# kwpa_ldmos2.net
KiCad netlist of a schematic drawn in EAGLE
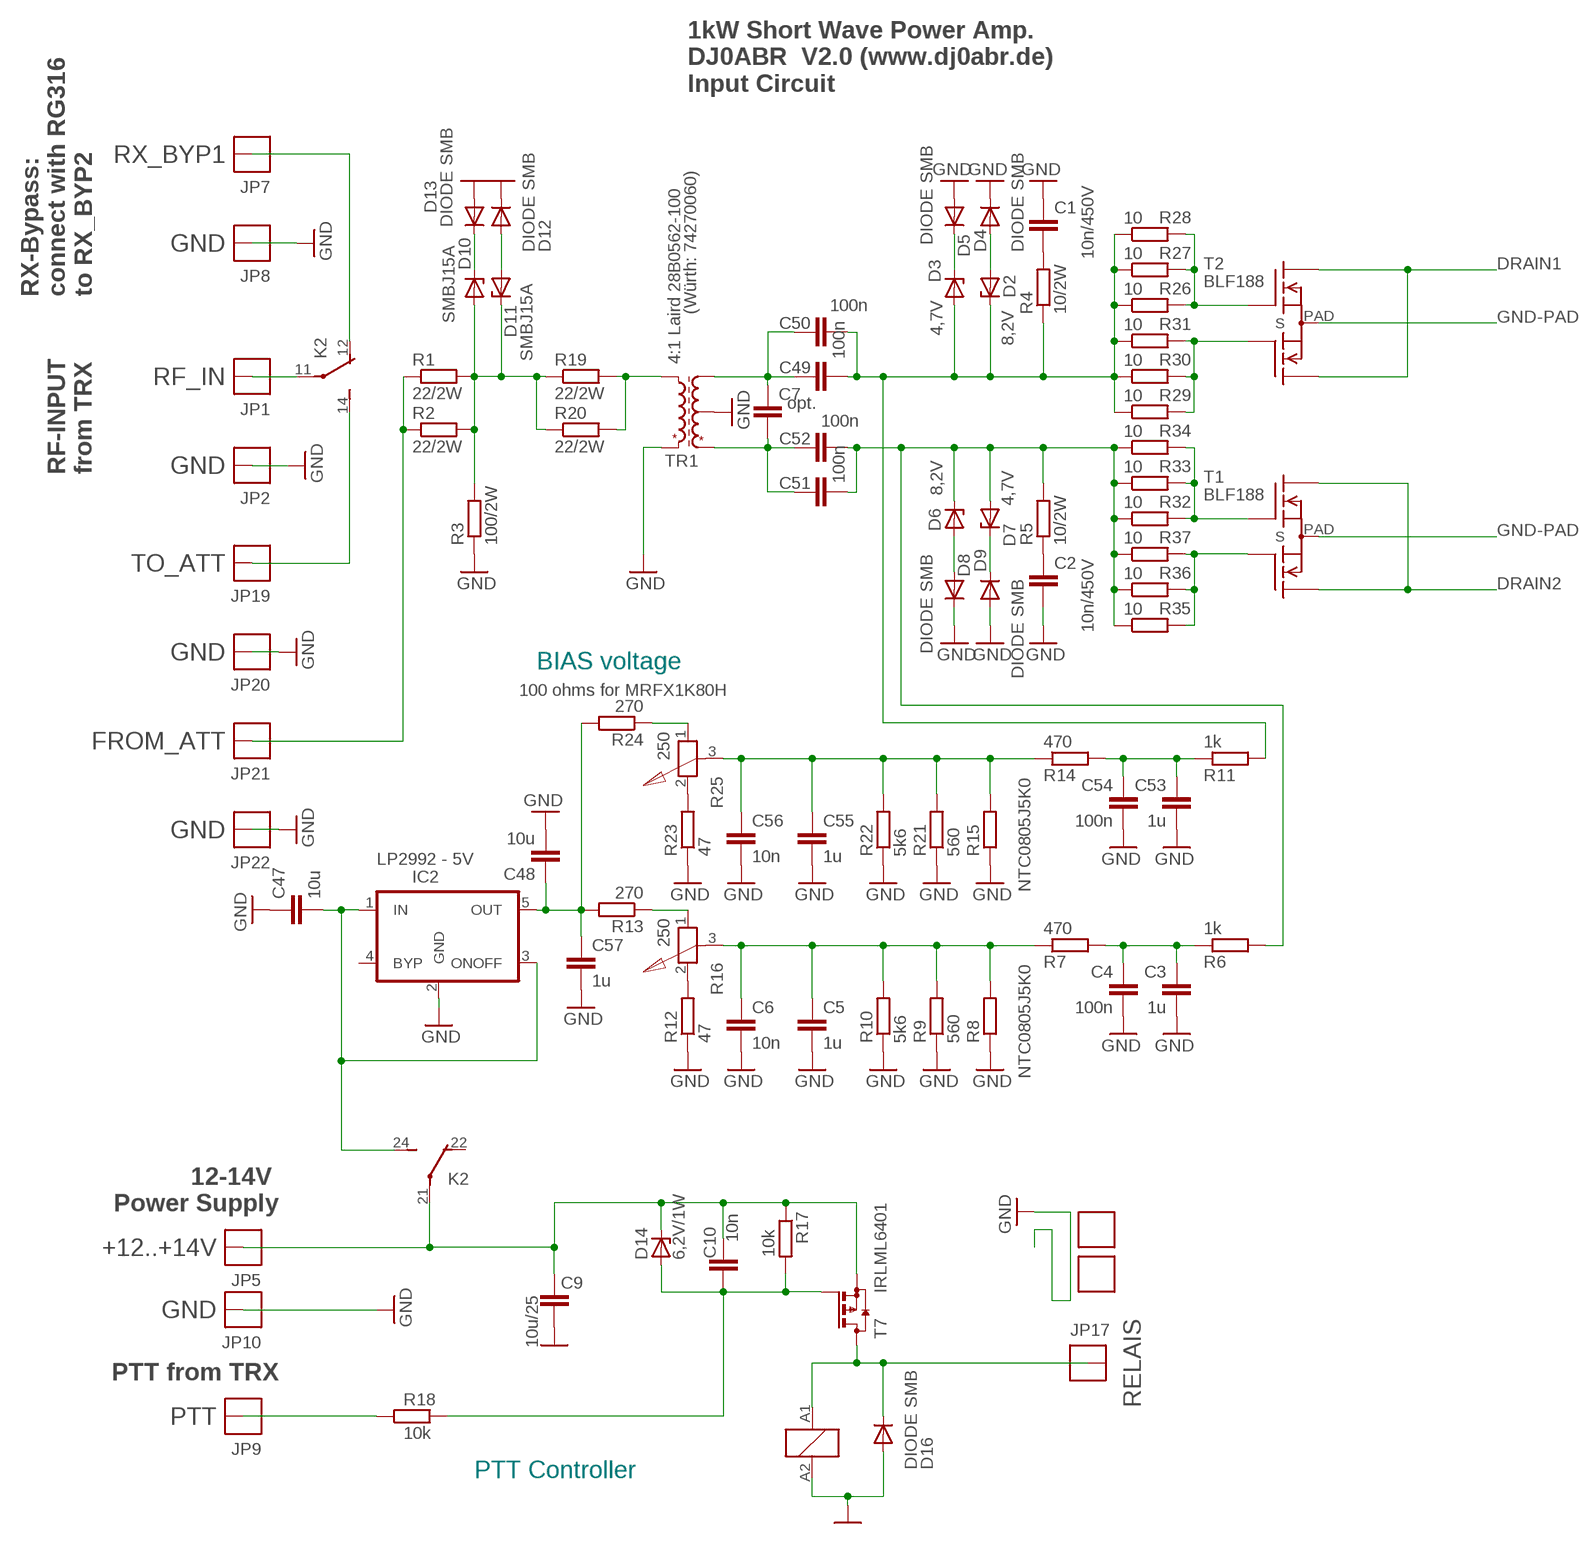
[diagram p0: schematic, sheet 1]
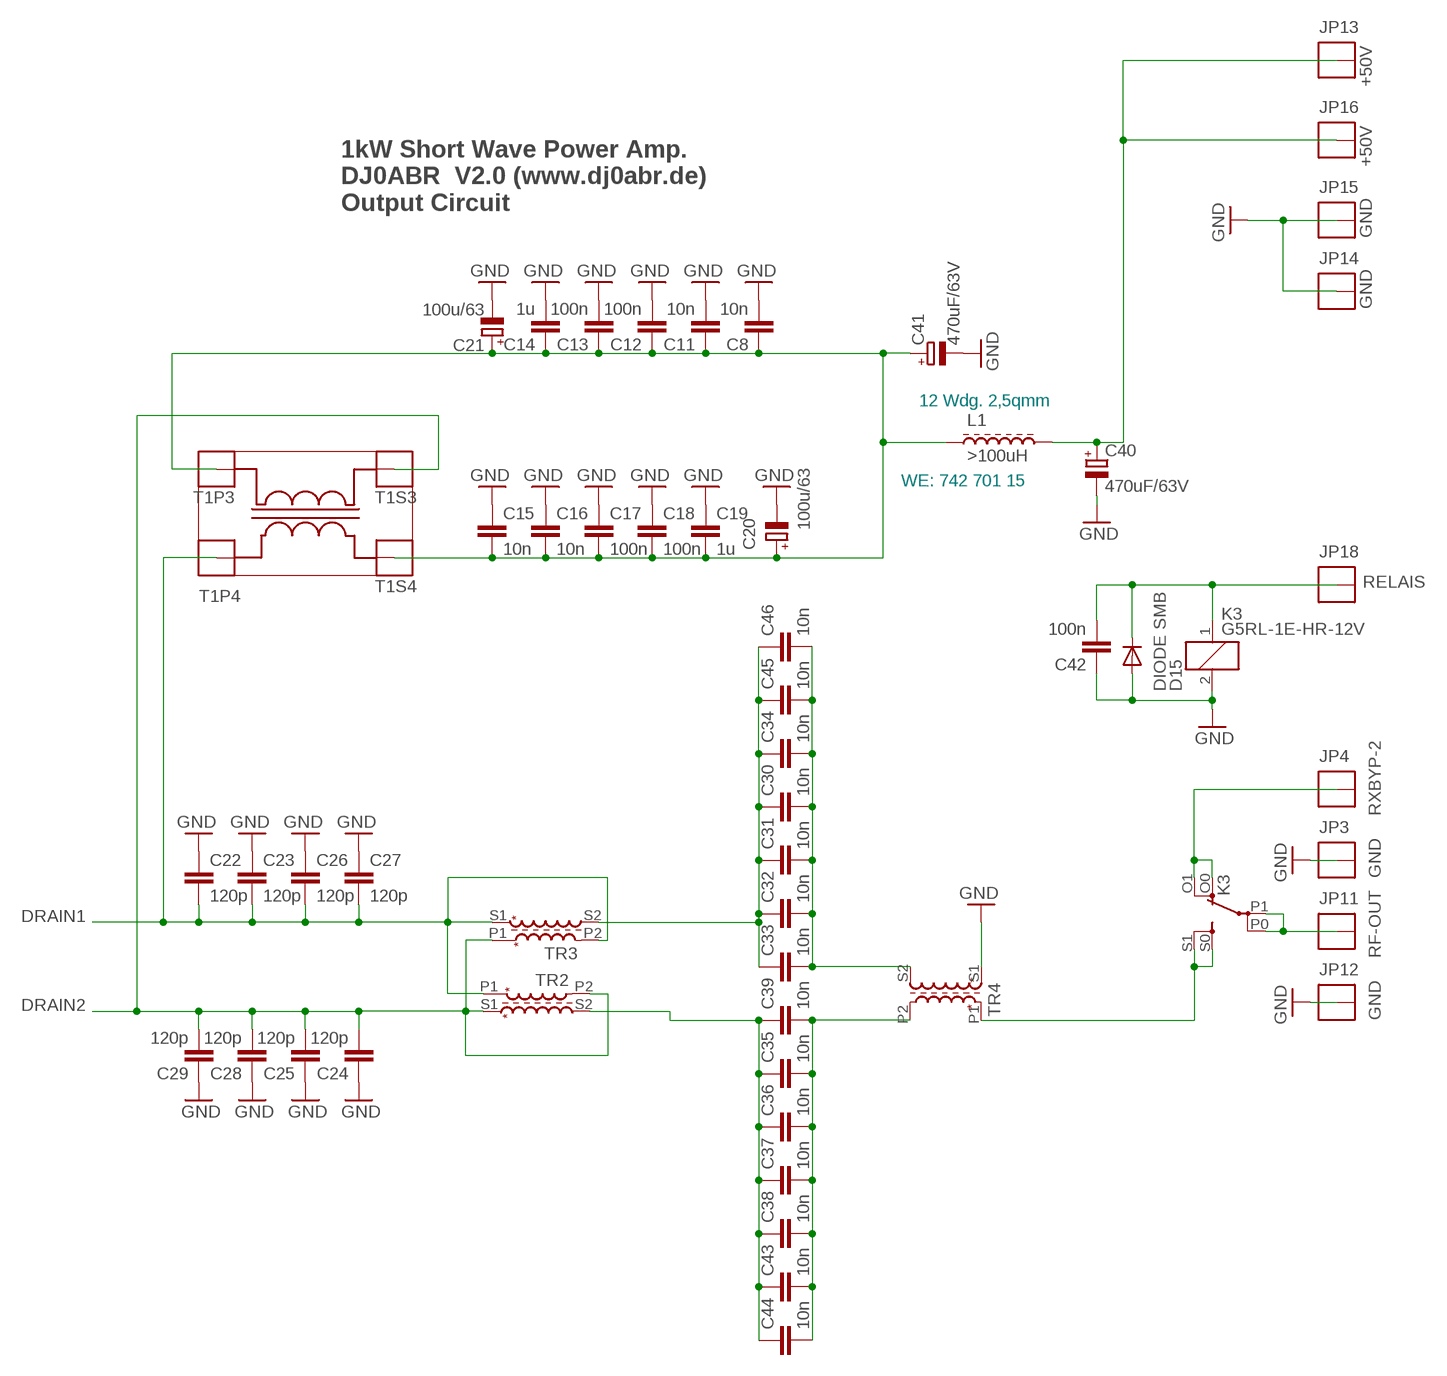
[diagram p1: schematic, sheet 2]

(export (version "E")
  (design (tool "Eeschema 10.0.6"))
  (components
    (comp (ref "C8")
      (value "10n")
      (footprint "eagle-import:C1812K")
      (libsource (lib "eagle-import") (part "C-EUC1812K"))
    )
    (comp (ref "C11")
      (value "10n")
      (footprint "eagle-import:C1812K")
      (libsource (lib "eagle-import") (part "C-EUC1812K"))
    )
    (comp (ref "C12")
      (value "100n")
      (footprint "eagle-import:C1812K")
      (libsource (lib "eagle-import") (part "C-EUC1812K"))
    )
    (comp (ref "C13")
      (value "100n")
      (footprint "eagle-import:C1812K")
      (libsource (lib "eagle-import") (part "C-EUC1812K"))
    )
    (comp (ref "C14")
      (value "1u")
      (footprint "eagle-import:C1812K")
      (libsource (lib "eagle-import") (part "C-EUC1812K"))
    )
    (comp (ref "C15")
      (value "10n")
      (footprint "eagle-import:C1812K")
      (libsource (lib "eagle-import") (part "C-EUC1812K"))
    )
    (comp (ref "C16")
      (value "10n")
      (footprint "eagle-import:C1812K")
      (libsource (lib "eagle-import") (part "C-EUC1812K"))
    )
    (comp (ref "C17")
      (value "100n")
      (footprint "eagle-import:C1812K")
      (libsource (lib "eagle-import") (part "C-EUC1812K"))
    )
    (comp (ref "C18")
      (value "100n")
      (footprint "eagle-import:C1812K")
      (libsource (lib "eagle-import") (part "C-EUC1812K"))
    )
    (comp (ref "C19")
      (value "1u")
      (footprint "eagle-import:C1812K")
      (libsource (lib "eagle-import") (part "C-EUC1812K"))
    )
    (comp (ref "C20")
      (value "100u/63")
      (footprint "eagle-import:153CLV-1014")
      (libsource (lib "eagle-import") (part "CPOL-EU153CLV-1014"))
    )
    (comp (ref "C21")
      (value "100u/63")
      (footprint "eagle-import:153CLV-1014")
      (libsource (lib "eagle-import") (part "CPOL-EU153CLV-1014"))
    )
    (comp (ref "C22")
      (value "120p")
      (footprint "eagle-import:C1812K")
      (libsource (lib "eagle-import") (part "C-EUC1812K"))
    )
    (comp (ref "C23")
      (value "120p")
      (footprint "eagle-import:C1812K")
      (libsource (lib "eagle-import") (part "C-EUC1812K"))
    )
    (comp (ref "C24")
      (value "120p")
      (footprint "eagle-import:C1812K")
      (libsource (lib "eagle-import") (part "C-EUC1812K"))
    )
    (comp (ref "C25")
      (value "120p")
      (footprint "eagle-import:C1812K")
      (libsource (lib "eagle-import") (part "C-EUC1812K"))
    )
    (comp (ref "C26")
      (value "120p")
      (footprint "eagle-import:C1812K")
      (libsource (lib "eagle-import") (part "C-EUC1812K"))
    )
    (comp (ref "C27")
      (value "120p")
      (footprint "eagle-import:C1812K")
      (libsource (lib "eagle-import") (part "C-EUC1812K"))
    )
    (comp (ref "C28")
      (value "120p")
      (footprint "eagle-import:C1812K")
      (libsource (lib "eagle-import") (part "C-EUC1812K"))
    )
    (comp (ref "C29")
      (value "120p")
      (footprint "eagle-import:C1812K")
      (libsource (lib "eagle-import") (part "C-EUC1812K"))
    )
    (comp (ref "C30")
      (value "10n")
      (footprint "eagle-import:C1210K")
      (libsource (lib "eagle-import") (part "C-EUC1210K"))
    )
    (comp (ref "C31")
      (value "10n")
      (footprint "eagle-import:C1210K")
      (libsource (lib "eagle-import") (part "C-EUC1210K"))
    )
    (comp (ref "C32")
      (value "10n")
      (footprint "eagle-import:C1210K")
      (libsource (lib "eagle-import") (part "C-EUC1210K"))
    )
    (comp (ref "C33")
      (value "10n")
      (footprint "eagle-import:C1210K")
      (libsource (lib "eagle-import") (part "C-EUC1210K"))
    )
    (comp (ref "C34")
      (value "10n")
      (footprint "eagle-import:C1210K")
      (libsource (lib "eagle-import") (part "C-EUC1210K"))
    )
    (comp (ref "C35")
      (value "10n")
      (footprint "eagle-import:C1210K")
      (libsource (lib "eagle-import") (part "C-EUC1210K"))
    )
    (comp (ref "C36")
      (value "10n")
      (footprint "eagle-import:C1210K")
      (libsource (lib "eagle-import") (part "C-EUC1210K"))
    )
    (comp (ref "C37")
      (value "10n")
      (footprint "eagle-import:C1210K")
      (libsource (lib "eagle-import") (part "C-EUC1210K"))
    )
    (comp (ref "C38")
      (value "10n")
      (footprint "eagle-import:C1210K")
      (libsource (lib "eagle-import") (part "C-EUC1210K"))
    )
    (comp (ref "C39")
      (value "10n")
      (footprint "eagle-import:C1210K")
      (libsource (lib "eagle-import") (part "C-EUC1210K"))
    )
    (comp (ref "C40")
      (value "470uF/63V")
      (footprint "eagle-import:E5-13")
      (libsource (lib "eagle-import") (part "CPOL-EUE5-13"))
    )
    (comp (ref "C41")
      (value "470uF/63V")
      (footprint "eagle-import:E5-13")
      (libsource (lib "eagle-import") (part "CPOL-EUE5-13"))
    )
    (comp (ref "C42")
      (value "100n")
      (footprint "eagle-import:C0603K")
      (libsource (lib "eagle-import") (part "C-EUC0603K"))
    )
    (comp (ref "C43")
      (value "10n")
      (footprint "eagle-import:C1210K")
      (libsource (lib "eagle-import") (part "C-EUC1210K"))
    )
    (comp (ref "C44")
      (value "10n")
      (footprint "eagle-import:C1210K")
      (libsource (lib "eagle-import") (part "C-EUC1210K"))
    )
    (comp (ref "C45")
      (value "10n")
      (footprint "eagle-import:C1210K")
      (libsource (lib "eagle-import") (part "C-EUC1210K"))
    )
    (comp (ref "C46")
      (value "10n")
      (footprint "eagle-import:C1210K")
      (libsource (lib "eagle-import") (part "C-EUC1210K"))
    )
    (comp (ref "D15")
      (value "DIODE SMB")
      (footprint "eagle-import:SMB")
      (libsource (lib "eagle-import") (part "DIODE-SMB"))
    )
    (comp (ref "JP3")
      (value "GND")
      (footprint "eagle-import:THICKPIN")
      (libsource (lib "eagle-import") (part "THICKPINSQUARE"))
    )
    (comp (ref "JP4")
      (value "RXBYP-2")
      (footprint "eagle-import:THICKPIN")
      (libsource (lib "eagle-import") (part "THICKPINSQUARE"))
    )
    (comp (ref "JP11")
      (value "RF-OUT")
      (footprint "eagle-import:THICKPIN")
      (libsource (lib "eagle-import") (part "THICKPINSQUARE"))
    )
    (comp (ref "JP12")
      (value "GND")
      (footprint "eagle-import:THICKPIN")
      (libsource (lib "eagle-import") (part "THICKPINSQUARE"))
    )
    (comp (ref "JP13")
      (value "+50V")
      (footprint "eagle-import:THICKPIN")
      (libsource (lib "eagle-import") (part "THICKPINSQUARE"))
    )
    (comp (ref "JP14")
      (value "GND")
      (footprint "eagle-import:THICKPIN")
      (libsource (lib "eagle-import") (part "THICKPINSQUARE"))
    )
    (comp (ref "JP15")
      (value "GND")
      (footprint "eagle-import:THICKPIN")
      (libsource (lib "eagle-import") (part "THICKPINSQUARE"))
    )
    (comp (ref "JP16")
      (value "+50V")
      (footprint "eagle-import:THICKPIN")
      (libsource (lib "eagle-import") (part "THICKPINSQUARE"))
    )
    (comp (ref "JP18")
      (value "RELAIS")
      (footprint "eagle-import:THICKPIN")
      (libsource (lib "eagle-import") (part "THICKPINSQUARE"))
    )
    (comp (ref "K3")
      (value "G5RL-1E-HR-12V")
      (footprint "eagle-import:G2RE")
      (libsource (lib "eagle-import") (part "G2RE"))
    )
    (comp (ref "L1")
      (value ">100uH")
      (footprint "eagle-import:KERN90_STEHEND_2PIN")
      (libsource (lib "eagle-import") (part "SPULE_1W30X12"))
    )
    (comp (ref "T1P3")
      (value "THICKPINSMD2,5X4")
      (footprint "eagle-import:SMDPAD2,5X4")
      (libsource (lib "eagle-import") (part "THICKPINSMD2,5X4"))
    )
    (comp (ref "T1P4")
      (value "THICKPINSMD2,5X4")
      (footprint "eagle-import:SMDPAD2,5X4")
      (libsource (lib "eagle-import") (part "THICKPINSMD2,5X4"))
    )
    (comp (ref "T1S3")
      (value "THICKPINSMD2,5X4")
      (footprint "eagle-import:SMDPAD2,5X4")
      (libsource (lib "eagle-import") (part "THICKPINSMD2,5X4"))
    )
    (comp (ref "T1S4")
      (value "THICKPINSMD2,5X4")
      (footprint "eagle-import:SMDPAD2,5X4")
      (libsource (lib "eagle-import") (part "THICKPINSMD2,5X4"))
    )
    (comp (ref "TR2")
      (value "TRAFO_1W_1W_GERADE_DOPPELROHR")
      (footprint "eagle-import:DOPPELRINGKERN")
      (libsource (lib "eagle-import") (part "TRAFO_1W_1W_GERADE_DOPPELROHR"))
    )
    (comp (ref "TR3")
      (value "TRAFO_1W_1W_GERADE_DOPPELROHRREVERSE")
      (footprint "eagle-import:DOPPELRINGKERN_REV")
      (libsource (lib "eagle-import") (part "TRAFO_1W_1W_GERADE_DOPPELROHRREVERSE"))
    )
    (comp (ref "TR4")
      (value "TRAFO_1W_1WMANTEL_STEHEND")
      (footprint "eagle-import:DOPPELLMANTEL_STEHEND")
      (libsource (lib "eagle-import") (part "TRAFO_1W_1WMANTEL_STEHEND"))
    )
    (comp (ref "C1")
      (value "10n/450V")
      (footprint "eagle-import:C1206K")
      (libsource (lib "eagle-import") (part "C-EUC1206K"))
    )
    (comp (ref "C2")
      (value "10n/450V")
      (footprint "eagle-import:C1206K")
      (libsource (lib "eagle-import") (part "C-EUC1206K"))
    )
    (comp (ref "C3")
      (value "1u")
      (footprint "eagle-import:C0603K")
      (libsource (lib "eagle-import") (part "C-EUC0603K"))
    )
    (comp (ref "C4")
      (value "100n")
      (footprint "eagle-import:C0603K")
      (libsource (lib "eagle-import") (part "C-EUC0603K"))
    )
    (comp (ref "C5")
      (value "1u")
      (footprint "eagle-import:C0603K")
      (libsource (lib "eagle-import") (part "C-EUC0603K"))
    )
    (comp (ref "C6")
      (value "10n")
      (footprint "eagle-import:C0603K")
      (libsource (lib "eagle-import") (part "C-EUC0603K"))
    )
    (comp (ref "C7")
      (value "opt.")
      (footprint "eagle-import:C1206K")
      (libsource (lib "eagle-import") (part "C-EUC1206K"))
    )
    (comp (ref "C9")
      (value "10u/25")
      (footprint "eagle-import:C0805K")
      (libsource (lib "eagle-import") (part "C-EUC0805K"))
    )
    (comp (ref "C10")
      (value "10n")
      (footprint "eagle-import:C0603K")
      (libsource (lib "eagle-import") (part "C-EUC0603K"))
    )
    (comp (ref "C47")
      (value "10u")
      (footprint "eagle-import:C0805K")
      (libsource (lib "eagle-import") (part "C-EUC0805K"))
    )
    (comp (ref "C48")
      (value "10u")
      (footprint "eagle-import:C0603K")
      (libsource (lib "eagle-import") (part "C-EUC0603K"))
    )
    (comp (ref "C49")
      (value "100n")
      (footprint "eagle-import:C1812K")
      (libsource (lib "eagle-import") (part "C-EUC1812K"))
    )
    (comp (ref "C50")
      (value "100n")
      (footprint "eagle-import:C1812K")
      (libsource (lib "eagle-import") (part "C-EUC1812K"))
    )
    (comp (ref "C51")
      (value "100n")
      (footprint "eagle-import:C1812K")
      (libsource (lib "eagle-import") (part "C-EUC1812K"))
    )
    (comp (ref "C52")
      (value "100n")
      (footprint "eagle-import:C1812K")
      (libsource (lib "eagle-import") (part "C-EUC1812K"))
    )
    (comp (ref "C53")
      (value "1u")
      (footprint "eagle-import:C0603K")
      (libsource (lib "eagle-import") (part "C-EUC0603K"))
    )
    (comp (ref "C54")
      (value "100n")
      (footprint "eagle-import:C0603K")
      (libsource (lib "eagle-import") (part "C-EUC0603K"))
    )
    (comp (ref "C55")
      (value "1u")
      (footprint "eagle-import:C0603K")
      (libsource (lib "eagle-import") (part "C-EUC0603K"))
    )
    (comp (ref "C56")
      (value "10n")
      (footprint "eagle-import:C0603K")
      (libsource (lib "eagle-import") (part "C-EUC0603K"))
    )
    (comp (ref "C57")
      (value "1u")
      (footprint "eagle-import:C0603K")
      (libsource (lib "eagle-import") (part "C-EUC0603K"))
    )
    (comp (ref "D2")
      (value "8,2V")
      (footprint "eagle-import:SMA")
      (libsource (lib "eagle-import") (part "ZPYSMA"))
    )
    (comp (ref "D3")
      (value "4,7V")
      (footprint "eagle-import:SMA")
      (libsource (lib "eagle-import") (part "ZPYSMA"))
    )
    (comp (ref "D4")
      (value "DIODE SMB")
      (footprint "eagle-import:SMB")
      (libsource (lib "eagle-import") (part "DIODE-SMB"))
    )
    (comp (ref "D5")
      (value "DIODE SMB")
      (footprint "eagle-import:SMB")
      (libsource (lib "eagle-import") (part "DIODE-SMB"))
    )
    (comp (ref "D6")
      (value "8,2V")
      (footprint "eagle-import:SMA")
      (libsource (lib "eagle-import") (part "ZPYSMA"))
    )
    (comp (ref "D7")
      (value "4,7V")
      (footprint "eagle-import:SMA")
      (libsource (lib "eagle-import") (part "ZPYSMA"))
    )
    (comp (ref "D8")
      (value "DIODE SMB")
      (footprint "eagle-import:SMB")
      (libsource (lib "eagle-import") (part "DIODE-SMB"))
    )
    (comp (ref "D9")
      (value "DIODE SMB")
      (footprint "eagle-import:SMB")
      (libsource (lib "eagle-import") (part "DIODE-SMB"))
    )
    (comp (ref "D10")
      (value "SMBJ15A")
      (footprint "eagle-import:SMA")
      (libsource (lib "eagle-import") (part "ZPYSMA"))
    )
    (comp (ref "D11")
      (value "SMBJ15A")
      (footprint "eagle-import:SMA")
      (libsource (lib "eagle-import") (part "ZPYSMA"))
    )
    (comp (ref "D12")
      (value "DIODE SMB")
      (footprint "eagle-import:SMB")
      (libsource (lib "eagle-import") (part "DIODE-SMB"))
    )
    (comp (ref "D13")
      (value "DIODE SMB")
      (footprint "eagle-import:SMB")
      (libsource (lib "eagle-import") (part "DIODE-SMB"))
    )
    (comp (ref "D14")
      (value "6,2V/1W")
      (footprint "eagle-import:SMA")
      (libsource (lib "eagle-import") (part "ZPYSMA"))
    )
    (comp (ref "D16")
      (value "DIODE SMB")
      (footprint "eagle-import:SMB")
      (libsource (lib "eagle-import") (part "DIODE-SMB"))
    )
    (comp (ref "FID1")
      (value "FIDUCIAL")
      (footprint "eagle-import:FIDUCIAL")
      (libsource (lib "eagle-import") (part "FIDUCIAL"))
    )
    (comp (ref "FID2")
      (value "FIDUCIAL")
      (footprint "eagle-import:FIDUCIAL")
      (libsource (lib "eagle-import") (part "FIDUCIAL"))
    )
    (comp (ref "H1")
      (value "HOLE_32")
      (footprint "eagle-import:HOLE32")
      (libsource (lib "eagle-import") (part "HOLE_32"))
    )
    (comp (ref "H2")
      (value "HOLE_32")
      (footprint "eagle-import:HOLE32")
      (libsource (lib "eagle-import") (part "HOLE_32"))
    )
    (comp (ref "H3")
      (value "HOLE_32")
      (footprint "eagle-import:HOLE32")
      (libsource (lib "eagle-import") (part "HOLE_32"))
    )
    (comp (ref "H4")
      (value "HOLE_32")
      (footprint "eagle-import:HOLE32")
      (libsource (lib "eagle-import") (part "HOLE_32"))
    )
    (comp (ref "H5")
      (value "HOLE_32")
      (footprint "eagle-import:HOLE32")
      (libsource (lib "eagle-import") (part "HOLE_32"))
    )
    (comp (ref "H6")
      (value "HOLE_32")
      (footprint "eagle-import:HOLE32")
      (libsource (lib "eagle-import") (part "HOLE_32"))
    )
    (comp (ref "H7")
      (value "HOLE_32")
      (footprint "eagle-import:HOLE32")
      (libsource (lib "eagle-import") (part "HOLE_32"))
    )
    (comp (ref "H8")
      (value "HOLE_32")
      (footprint "eagle-import:HOLE32")
      (libsource (lib "eagle-import") (part "HOLE_32"))
    )
    (comp (ref "H9")
      (value "HOLE_32")
      (footprint "eagle-import:HOLE32")
      (libsource (lib "eagle-import") (part "HOLE_32"))
    )
    (comp (ref "H10")
      (value "HOLE_32")
      (footprint "eagle-import:HOLE32")
      (libsource (lib "eagle-import") (part "HOLE_32"))
    )
    (comp (ref "H11")
      (value "HOLE_32")
      (footprint "eagle-import:HOLE32")
      (libsource (lib "eagle-import") (part "HOLE_32"))
    )
    (comp (ref "H12")
      (value "HOLE_32")
      (footprint "eagle-import:HOLE32")
      (libsource (lib "eagle-import") (part "HOLE_32"))
    )
    (comp (ref "H13")
      (value "HOLE_32")
      (footprint "eagle-import:HOLE32")
      (libsource (lib "eagle-import") (part "HOLE_32"))
    )
    (comp (ref "H14")
      (value "HOLE_32")
      (footprint "eagle-import:HOLE32")
      (libsource (lib "eagle-import") (part "HOLE_32"))
    )
    (comp (ref "IC2")
      (value "LP2992 - 5V")
      (footprint "eagle-import:SOT23-5")
      (libsource (lib "eagle-import") (part "UREG5"))
    )
    (comp (ref "JP1")
      (value "RF_IN")
      (footprint "eagle-import:THICKPIN")
      (libsource (lib "eagle-import") (part "THICKPINSQUARE"))
    )
    (comp (ref "JP2")
      (value "GND")
      (footprint "eagle-import:THICKPIN")
      (libsource (lib "eagle-import") (part "THICKPINSQUARE"))
    )
    (comp (ref "JP5")
      (value "+12..+14V")
      (footprint "eagle-import:THICKPIN")
      (libsource (lib "eagle-import") (part "THICKPINSQUARE"))
    )
    (comp (ref "JP7")
      (value "RX_BYP1")
      (footprint "eagle-import:THICKPIN")
      (libsource (lib "eagle-import") (part "THICKPINSQUARE"))
    )
    (comp (ref "JP8")
      (value "GND")
      (footprint "eagle-import:THICKPIN")
      (libsource (lib "eagle-import") (part "THICKPINSQUARE"))
    )
    (comp (ref "JP9")
      (value "PTT")
      (footprint "eagle-import:THICKPIN")
      (libsource (lib "eagle-import") (part "THICKPINSQUARE"))
    )
    (comp (ref "JP10")
      (value "GND")
      (footprint "eagle-import:THICKPIN")
      (libsource (lib "eagle-import") (part "THICKPINSQUARE"))
    )
    (comp (ref "JP17")
      (value "RELAIS")
      (footprint "eagle-import:THICKPIN")
      (libsource (lib "eagle-import") (part "THICKPINSQUARE"))
    )
    (comp (ref "JP19")
      (value "TO_ATT")
      (footprint "eagle-import:THICKPIN")
      (libsource (lib "eagle-import") (part "THICKPINSQUARE"))
    )
    (comp (ref "JP20")
      (value "GND")
      (footprint "eagle-import:THICKPIN")
      (libsource (lib "eagle-import") (part "THICKPINSQUARE"))
    )
    (comp (ref "JP21")
      (value "FROM_ATT")
      (footprint "eagle-import:THICKPIN")
      (libsource (lib "eagle-import") (part "THICKPINSQUARE"))
    )
    (comp (ref "JP22")
      (value "GND")
      (footprint "eagle-import:THICKPIN")
      (libsource (lib "eagle-import") (part "THICKPINSQUARE"))
    )
    (comp (ref "K2")
      (value "FINDER-30.22")
      (footprint "eagle-import:FINDER-30.22")
      (libsource (lib "eagle-import") (part "FINDER-30.22"))
    )
    (comp (ref "R1")
      (value "22/2W")
      (footprint "eagle-import:R2512")
      (libsource (lib "eagle-import") (part "R-EU_R2512"))
    )
    (comp (ref "R2")
      (value "22/2W")
      (footprint "eagle-import:R2512")
      (libsource (lib "eagle-import") (part "R-EU_R2512"))
    )
    (comp (ref "R3")
      (value "100/2W")
      (footprint "eagle-import:R2512")
      (libsource (lib "eagle-import") (part "R-EU_R2512"))
    )
    (comp (ref "R4")
      (value "10/2W")
      (footprint "eagle-import:R2512")
      (libsource (lib "eagle-import") (part "R-EU_R2512"))
    )
    (comp (ref "R5")
      (value "10/2W")
      (footprint "eagle-import:R2512")
      (libsource (lib "eagle-import") (part "R-EU_R2512"))
    )
    (comp (ref "R6")
      (value "1k")
      (footprint "eagle-import:R0603")
      (libsource (lib "eagle-import") (part "R-EU_R0603"))
    )
    (comp (ref "R7")
      (value "470")
      (footprint "eagle-import:R0603")
      (libsource (lib "eagle-import") (part "R-EU_R0603"))
    )
    (comp (ref "R8")
      (value "NTC0805J5K0")
      (footprint "eagle-import:R0805")
      (libsource (lib "eagle-import") (part "R-EU_R0805"))
    )
    (comp (ref "R9")
      (value "560")
      (footprint "eagle-import:R0603")
      (libsource (lib "eagle-import") (part "R-EU_R0603"))
    )
    (comp (ref "R10")
      (value "5k6")
      (footprint "eagle-import:R0603")
      (libsource (lib "eagle-import") (part "R-EU_R0603"))
    )
    (comp (ref "R11")
      (value "1k")
      (footprint "eagle-import:R0603")
      (libsource (lib "eagle-import") (part "R-EU_R0603"))
    )
    (comp (ref "R12")
      (value "47")
      (footprint "eagle-import:R0603")
      (libsource (lib "eagle-import") (part "R-EU_R0603"))
    )
    (comp (ref "R13")
      (value "270")
      (footprint "eagle-import:R0603")
      (libsource (lib "eagle-import") (part "R-EU_R0603"))
    )
    (comp (ref "R14")
      (value "470")
      (footprint "eagle-import:R0603")
      (libsource (lib "eagle-import") (part "R-EU_R0603"))
    )
    (comp (ref "R15")
      (value "NTC0805J5K0")
      (footprint "eagle-import:R0805")
      (libsource (lib "eagle-import") (part "R-EU_R0805"))
    )
    (comp (ref "R16")
      (value "250")
      (footprint "eagle-import:MINIPOTI")
      (libsource (lib "eagle-import") (part "MINIPOTI-S"))
    )
    (comp (ref "R17")
      (value "10k")
      (footprint "eagle-import:R0603")
      (libsource (lib "eagle-import") (part "R-EU_R0603"))
    )
    (comp (ref "R18")
      (value "10k")
      (footprint "eagle-import:R0603")
      (libsource (lib "eagle-import") (part "R-EU_R0603"))
    )
    (comp (ref "R19")
      (value "22/2W")
      (footprint "eagle-import:R2512")
      (libsource (lib "eagle-import") (part "R-EU_R2512"))
    )
    (comp (ref "R20")
      (value "22/2W")
      (footprint "eagle-import:R2512")
      (libsource (lib "eagle-import") (part "R-EU_R2512"))
    )
    (comp (ref "R21")
      (value "560")
      (footprint "eagle-import:R0603")
      (libsource (lib "eagle-import") (part "R-EU_R0603"))
    )
    (comp (ref "R22")
      (value "5k6")
      (footprint "eagle-import:R0603")
      (libsource (lib "eagle-import") (part "R-EU_R0603"))
    )
    (comp (ref "R23")
      (value "47")
      (footprint "eagle-import:R0603")
      (libsource (lib "eagle-import") (part "R-EU_R0603"))
    )
    (comp (ref "R24")
      (value "270")
      (footprint "eagle-import:R0603")
      (libsource (lib "eagle-import") (part "R-EU_R0603"))
    )
    (comp (ref "R25")
      (value "250")
      (footprint "eagle-import:MINIPOTI")
      (libsource (lib "eagle-import") (part "MINIPOTI-S"))
    )
    (comp (ref "R26")
      (value "10")
      (footprint "eagle-import:R1206")
      (libsource (lib "eagle-import") (part "R-EU_R1206"))
    )
    (comp (ref "R27")
      (value "10")
      (footprint "eagle-import:R1206")
      (libsource (lib "eagle-import") (part "R-EU_R1206"))
    )
    (comp (ref "R28")
      (value "10")
      (footprint "eagle-import:R1206")
      (libsource (lib "eagle-import") (part "R-EU_R1206"))
    )
    (comp (ref "R29")
      (value "10")
      (footprint "eagle-import:R1206")
      (libsource (lib "eagle-import") (part "R-EU_R1206"))
    )
    (comp (ref "R30")
      (value "10")
      (footprint "eagle-import:R1206")
      (libsource (lib "eagle-import") (part "R-EU_R1206"))
    )
    (comp (ref "R31")
      (value "10")
      (footprint "eagle-import:R1206")
      (libsource (lib "eagle-import") (part "R-EU_R1206"))
    )
    (comp (ref "R32")
      (value "10")
      (footprint "eagle-import:R1206")
      (libsource (lib "eagle-import") (part "R-EU_R1206"))
    )
    (comp (ref "R33")
      (value "10")
      (footprint "eagle-import:R1206")
      (libsource (lib "eagle-import") (part "R-EU_R1206"))
    )
    (comp (ref "R34")
      (value "10")
      (footprint "eagle-import:R1206")
      (libsource (lib "eagle-import") (part "R-EU_R1206"))
    )
    (comp (ref "R35")
      (value "10")
      (footprint "eagle-import:R1206")
      (libsource (lib "eagle-import") (part "R-EU_R1206"))
    )
    (comp (ref "R36")
      (value "10")
      (footprint "eagle-import:R1206")
      (libsource (lib "eagle-import") (part "R-EU_R1206"))
    )
    (comp (ref "R37")
      (value "10")
      (footprint "eagle-import:R1206")
      (libsource (lib "eagle-import") (part "R-EU_R1206"))
    )
    (comp (ref "T1")
      (value "BLF188")
      (footprint "eagle-import:BLF188")
      (libsource (lib "eagle-import") (part "BLF188"))
    )
    (comp (ref "T2")
      (value "BLF188")
      (footprint "eagle-import:BLF188")
      (libsource (lib "eagle-import") (part "BLF188"))
    )
    (comp (ref "T7")
      (value "IRLML6401")
      (footprint "eagle-import:SOT23")
      (libsource (lib "eagle-import") (part "BSS84"))
    )
    (comp (ref "TR1")
      (value "4:1 Laird 28B0562-100")
      (footprint "eagle-import:KW-INPUT_LAIRD_28B0562-100")
      (libsource (lib "eagle-import") (part "TRAFO_1W_2W_MIT_ANZAPFUNGKWPAINPUT"))
    )
  )
  (nets
    (net (code "1") (name "BYP") (class "Default")
      (node (ref "IC2") (pin "4") (pinfunction "BYP_4") (pintype "power_in"))
    )
    (net (code "2") (name "DRAIN1") (class "Default")
      (node (ref "C22") (pin "2") (pinfunction "2_2") (pintype "passive"))
      (node (ref "C23") (pin "2") (pinfunction "2_2") (pintype "passive"))
      (node (ref "C26") (pin "2") (pinfunction "2_2") (pintype "passive"))
      (node (ref "C27") (pin "2") (pinfunction "2_2") (pintype "passive"))
      (node (ref "T1P4") (pin "P$1") (pinfunction "1_P$1") (pintype "bidirectional"))
      (node (ref "T2") (pin "1") (pinfunction "D1_1") (pintype "passive"))
      (node (ref "T2") (pin "2") (pinfunction "D2_2") (pintype "passive"))
      (node (ref "TR2") (pin "P1") (pinfunction "P1_P1") (pintype "passive"))
      (node (ref "TR3") (pin "P2") (pinfunction "P2_P2") (pintype "passive"))
      (node (ref "TR3") (pin "S1") (pinfunction "S1_S1") (pintype "passive"))
    )
    (net (code "3") (name "DRAIN2") (class "Default")
      (node (ref "C24") (pin "2") (pinfunction "2_2") (pintype "passive"))
      (node (ref "C25") (pin "2") (pinfunction "2_2") (pintype "passive"))
      (node (ref "C28") (pin "2") (pinfunction "2_2") (pintype "passive"))
      (node (ref "C29") (pin "2") (pinfunction "2_2") (pintype "passive"))
      (node (ref "T1") (pin "1") (pinfunction "D1_1") (pintype "passive"))
      (node (ref "T1") (pin "2") (pinfunction "D2_2") (pintype "passive"))
      (node (ref "T1S3") (pin "P$1") (pinfunction "1_P$1") (pintype "bidirectional"))
      (node (ref "TR2") (pin "P2") (pinfunction "P2_P2") (pintype "passive"))
      (node (ref "TR2") (pin "S1") (pinfunction "S1_S1") (pintype "passive"))
      (node (ref "TR3") (pin "P1") (pinfunction "P1_P1") (pintype "passive"))
    )
    (net (code "4") (name "GND") (class "Default")
      (node (ref "C1") (pin "1") (pinfunction "1_1") (pintype "passive"))
      (node (ref "C11") (pin "2") (pinfunction "2_2") (pintype "passive"))
      (node (ref "C12") (pin "2") (pinfunction "2_2") (pintype "passive"))
      (node (ref "C13") (pin "2") (pinfunction "2_2") (pintype "passive"))
      (node (ref "C14") (pin "2") (pinfunction "2_2") (pintype "passive"))
      (node (ref "C15") (pin "1") (pinfunction "1_1") (pintype "passive"))
      (node (ref "C16") (pin "1") (pinfunction "1_1") (pintype "passive"))
      (node (ref "C17") (pin "1") (pinfunction "1_1") (pintype "passive"))
      (node (ref "C18") (pin "1") (pinfunction "1_1") (pintype "passive"))
      (node (ref "C19") (pin "1") (pinfunction "1_1") (pintype "passive"))
      (node (ref "C2") (pin "2") (pinfunction "2_2") (pintype "passive"))
      (node (ref "C20") (pin "-") (pinfunction "-_-") (pintype "passive"))
      (node (ref "C21") (pin "-") (pinfunction "-_-") (pintype "passive"))
      (node (ref "C22") (pin "1") (pinfunction "1_1") (pintype "passive"))
      (node (ref "C23") (pin "1") (pinfunction "1_1") (pintype "passive"))
      (node (ref "C24") (pin "1") (pinfunction "1_1") (pintype "passive"))
      (node (ref "C25") (pin "1") (pinfunction "1_1") (pintype "passive"))
      (node (ref "C26") (pin "1") (pinfunction "1_1") (pintype "passive"))
      (node (ref "C27") (pin "1") (pinfunction "1_1") (pintype "passive"))
      (node (ref "C28") (pin "1") (pinfunction "1_1") (pintype "passive"))
      (node (ref "C29") (pin "1") (pinfunction "1_1") (pintype "passive"))
      (node (ref "C3") (pin "2") (pinfunction "2_2") (pintype "passive"))
      (node (ref "C4") (pin "2") (pinfunction "2_2") (pintype "passive"))
      (node (ref "C40") (pin "-") (pinfunction "-_-") (pintype "passive"))
      (node (ref "C41") (pin "-") (pinfunction "-_-") (pintype "passive"))
      (node (ref "C42") (pin "1") (pinfunction "1_1") (pintype "passive"))
      (node (ref "C47") (pin "1") (pinfunction "1_1") (pintype "passive"))
      (node (ref "C48") (pin "2") (pinfunction "2_2") (pintype "passive"))
      (node (ref "C5") (pin "2") (pinfunction "2_2") (pintype "passive"))
      (node (ref "C53") (pin "2") (pinfunction "2_2") (pintype "passive"))
      (node (ref "C54") (pin "2") (pinfunction "2_2") (pintype "passive"))
      (node (ref "C55") (pin "2") (pinfunction "2_2") (pintype "passive"))
      (node (ref "C56") (pin "2") (pinfunction "2_2") (pintype "passive"))
      (node (ref "C57") (pin "2") (pinfunction "2_2") (pintype "passive"))
      (node (ref "C6") (pin "2") (pinfunction "2_2") (pintype "passive"))
      (node (ref "C8") (pin "2") (pinfunction "2_2") (pintype "passive"))
      (node (ref "C9") (pin "2") (pinfunction "2_2") (pintype "passive"))
      (node (ref "D12") (pin "C") (pinfunction "C_C") (pintype "passive"))
      (node (ref "D13") (pin "A") (pinfunction "A_A") (pintype "passive"))
      (node (ref "D15") (pin "A") (pinfunction "A_A") (pintype "passive"))
      (node (ref "D16") (pin "A") (pinfunction "A_A") (pintype "passive"))
      (node (ref "D4") (pin "C") (pinfunction "C_C") (pintype "passive"))
      (node (ref "D5") (pin "A") (pinfunction "A_A") (pintype "passive"))
      (node (ref "D8") (pin "C") (pinfunction "C_C") (pintype "passive"))
      (node (ref "D9") (pin "A") (pinfunction "A_A") (pintype "passive"))
      (node (ref "H1") (pin "P$1") (pinfunction "P$1_P$1") (pintype "bidirectional"))
      (node (ref "H10") (pin "P$1") (pinfunction "P$1_P$1") (pintype "bidirectional"))
      (node (ref "H11") (pin "P$1") (pinfunction "P$1_P$1") (pintype "bidirectional"))
      (node (ref "H12") (pin "P$1") (pinfunction "P$1_P$1") (pintype "bidirectional"))
      (node (ref "H13") (pin "P$1") (pinfunction "P$1_P$1") (pintype "bidirectional"))
      (node (ref "H14") (pin "P$1") (pinfunction "P$1_P$1") (pintype "bidirectional"))
      (node (ref "H2") (pin "P$1") (pinfunction "P$1_P$1") (pintype "bidirectional"))
      (node (ref "H3") (pin "P$1") (pinfunction "P$1_P$1") (pintype "bidirectional"))
      (node (ref "H4") (pin "P$1") (pinfunction "P$1_P$1") (pintype "bidirectional"))
      (node (ref "H5") (pin "P$1") (pinfunction "P$1_P$1") (pintype "bidirectional"))
      (node (ref "H6") (pin "P$1") (pinfunction "P$1_P$1") (pintype "bidirectional"))
      (node (ref "H7") (pin "P$1") (pinfunction "P$1_P$1") (pintype "bidirectional"))
      (node (ref "H8") (pin "P$1") (pinfunction "P$1_P$1") (pintype "bidirectional"))
      (node (ref "H9") (pin "P$1") (pinfunction "P$1_P$1") (pintype "bidirectional"))
      (node (ref "IC2") (pin "2") (pinfunction "GND_2") (pintype "power_in"))
      (node (ref "JP10") (pin "1") (pinfunction "1_1") (pintype "bidirectional"))
      (node (ref "JP12") (pin "1") (pinfunction "1_1") (pintype "bidirectional"))
      (node (ref "JP14") (pin "1") (pinfunction "1_1") (pintype "bidirectional"))
      (node (ref "JP15") (pin "1") (pinfunction "1_1") (pintype "bidirectional"))
      (node (ref "JP2") (pin "1") (pinfunction "1_1") (pintype "bidirectional"))
      (node (ref "JP20") (pin "1") (pinfunction "1_1") (pintype "bidirectional"))
      (node (ref "JP22") (pin "1") (pinfunction "1_1") (pintype "bidirectional"))
      (node (ref "JP3") (pin "1") (pinfunction "1_1") (pintype "bidirectional"))
      (node (ref "JP8") (pin "1") (pinfunction "1_1") (pintype "bidirectional"))
      (node (ref "K2") (pin "A2") (pinfunction "2_A2") (pintype "passive"))
      (node (ref "K3") (pin "2") (pinfunction "2_2") (pintype "passive"))
      (node (ref "R10") (pin "1") (pinfunction "1_1") (pintype "passive"))
      (node (ref "R12") (pin "1") (pinfunction "1_1") (pintype "passive"))
      (node (ref "R15") (pin "1") (pinfunction "1_1") (pintype "passive"))
      (node (ref "R21") (pin "1") (pinfunction "1_1") (pintype "passive"))
      (node (ref "R22") (pin "1") (pinfunction "1_1") (pintype "passive"))
      (node (ref "R23") (pin "1") (pinfunction "1_1") (pintype "passive"))
      (node (ref "R3") (pin "1") (pinfunction "1_1") (pintype "passive"))
      (node (ref "R8") (pin "1") (pinfunction "1_1") (pintype "passive"))
      (node (ref "R9") (pin "1") (pinfunction "1_1") (pintype "passive"))
      (node (ref "TR1") (pin "COM") (pinfunction "SM_COM") (pintype "passive"))
      (node (ref "TR1") (pin "GND") (pinfunction "P1_GND") (pintype "passive"))
      (node (ref "TR4") (pin "S1") (pinfunction "S1_S1") (pintype "passive"))
    )
    (net (code "5") (name "Net-(C1-Pad2)") (class "Default")
      (node (ref "C1") (pin "2") (pinfunction "2_2") (pintype "passive"))
      (node (ref "R4") (pin "2") (pinfunction "2_2") (pintype "passive"))
    )
    (net (code "6") (name "Net-(C2-Pad1)") (class "Default")
      (node (ref "C2") (pin "1") (pinfunction "1_1") (pintype "passive"))
      (node (ref "R5") (pin "1") (pinfunction "1_1") (pintype "passive"))
    )
    (net (code "7") (name "Net-(C3-Pad1)") (class "Default")
      (node (ref "C3") (pin "1") (pinfunction "1_1") (pintype "passive"))
      (node (ref "C4") (pin "1") (pinfunction "1_1") (pintype "passive"))
      (node (ref "R6") (pin "1") (pinfunction "1_1") (pintype "passive"))
      (node (ref "R7") (pin "2") (pinfunction "2_2") (pintype "passive"))
    )
    (net (code "8") (name "Net-(C5-Pad1)") (class "Default")
      (node (ref "C5") (pin "1") (pinfunction "1_1") (pintype "passive"))
      (node (ref "C6") (pin "1") (pinfunction "1_1") (pintype "passive"))
      (node (ref "R10") (pin "2") (pinfunction "2_2") (pintype "passive"))
      (node (ref "R16") (pin "3") (pinfunction "3_3") (pintype "passive"))
      (node (ref "R7") (pin "1") (pinfunction "1_1") (pintype "passive"))
      (node (ref "R8") (pin "2") (pinfunction "2_2") (pintype "passive"))
      (node (ref "R9") (pin "2") (pinfunction "2_2") (pintype "passive"))
    )
    (net (code "9") (name "Net-(C30-Pad1)") (class "Default")
      (node (ref "C30") (pin "1") (pinfunction "1_1") (pintype "passive"))
      (node (ref "C31") (pin "1") (pinfunction "1_1") (pintype "passive"))
      (node (ref "C32") (pin "1") (pinfunction "1_1") (pintype "passive"))
      (node (ref "C33") (pin "1") (pinfunction "1_1") (pintype "passive"))
      (node (ref "C34") (pin "1") (pinfunction "1_1") (pintype "passive"))
      (node (ref "C45") (pin "1") (pinfunction "1_1") (pintype "passive"))
      (node (ref "C46") (pin "1") (pinfunction "1_1") (pintype "passive"))
      (node (ref "TR3") (pin "S2") (pinfunction "S2_S2") (pintype "passive"))
    )
    (net (code "10") (name "Net-(C30-Pad2)") (class "Default")
      (node (ref "C30") (pin "2") (pinfunction "2_2") (pintype "passive"))
      (node (ref "C31") (pin "2") (pinfunction "2_2") (pintype "passive"))
      (node (ref "C32") (pin "2") (pinfunction "2_2") (pintype "passive"))
      (node (ref "C33") (pin "2") (pinfunction "2_2") (pintype "passive"))
      (node (ref "C34") (pin "2") (pinfunction "2_2") (pintype "passive"))
      (node (ref "C45") (pin "2") (pinfunction "2_2") (pintype "passive"))
      (node (ref "C46") (pin "2") (pinfunction "2_2") (pintype "passive"))
      (node (ref "TR4") (pin "S2") (pinfunction "S2_S2") (pintype "passive"))
    )
    (net (code "11") (name "Net-(C35-Pad1)") (class "Default")
      (node (ref "C35") (pin "1") (pinfunction "1_1") (pintype "passive"))
      (node (ref "C36") (pin "1") (pinfunction "1_1") (pintype "passive"))
      (node (ref "C37") (pin "1") (pinfunction "1_1") (pintype "passive"))
      (node (ref "C38") (pin "1") (pinfunction "1_1") (pintype "passive"))
      (node (ref "C39") (pin "1") (pinfunction "1_1") (pintype "passive"))
      (node (ref "C43") (pin "1") (pinfunction "1_1") (pintype "passive"))
      (node (ref "C44") (pin "1") (pinfunction "1_1") (pintype "passive"))
      (node (ref "TR2") (pin "S2") (pinfunction "S2_S2") (pintype "passive"))
    )
    (net (code "12") (name "Net-(C35-Pad2)") (class "Default")
      (node (ref "C35") (pin "2") (pinfunction "2_2") (pintype "passive"))
      (node (ref "C36") (pin "2") (pinfunction "2_2") (pintype "passive"))
      (node (ref "C37") (pin "2") (pinfunction "2_2") (pintype "passive"))
      (node (ref "C38") (pin "2") (pinfunction "2_2") (pintype "passive"))
      (node (ref "C39") (pin "2") (pinfunction "2_2") (pintype "passive"))
      (node (ref "C43") (pin "2") (pinfunction "2_2") (pintype "passive"))
      (node (ref "C44") (pin "2") (pinfunction "2_2") (pintype "passive"))
      (node (ref "TR4") (pin "P2") (pinfunction "P2_P2") (pintype "passive"))
    )
    (net (code "13") (name "Net-(C42-Pad2)") (class "Default")
      (node (ref "C42") (pin "2") (pinfunction "2_2") (pintype "passive"))
      (node (ref "D15") (pin "C") (pinfunction "C_C") (pintype "passive"))
      (node (ref "JP18") (pin "1") (pinfunction "1_1") (pintype "bidirectional"))
      (node (ref "K3") (pin "1") (pinfunction "1_1") (pintype "passive"))
    )
    (net (code "14") (name "Net-(C49-Pad2)") (class "Default")
      (node (ref "C49") (pin "2") (pinfunction "2_2") (pintype "passive"))
      (node (ref "C50") (pin "2") (pinfunction "2_2") (pintype "passive"))
      (node (ref "D2") (pin "C") (pinfunction "C_C") (pintype "passive"))
      (node (ref "D3") (pin "A") (pinfunction "A_A") (pintype "passive"))
      (node (ref "R11") (pin "2") (pinfunction "2_2") (pintype "passive"))
      (node (ref "R26") (pin "1") (pinfunction "1_1") (pintype "passive"))
      (node (ref "R27") (pin "1") (pinfunction "1_1") (pintype "passive"))
      (node (ref "R28") (pin "1") (pinfunction "1_1") (pintype "passive"))
      (node (ref "R29") (pin "1") (pinfunction "1_1") (pintype "passive"))
      (node (ref "R30") (pin "1") (pinfunction "1_1") (pintype "passive"))
      (node (ref "R31") (pin "1") (pinfunction "1_1") (pintype "passive"))
      (node (ref "R4") (pin "1") (pinfunction "1_1") (pintype "passive"))
    )
    (net (code "15") (name "Net-(C51-Pad2)") (class "Default")
      (node (ref "C51") (pin "2") (pinfunction "2_2") (pintype "passive"))
      (node (ref "C52") (pin "2") (pinfunction "2_2") (pintype "passive"))
      (node (ref "D6") (pin "C") (pinfunction "C_C") (pintype "passive"))
      (node (ref "D7") (pin "A") (pinfunction "A_A") (pintype "passive"))
      (node (ref "R32") (pin "1") (pinfunction "1_1") (pintype "passive"))
      (node (ref "R33") (pin "1") (pinfunction "1_1") (pintype "passive"))
      (node (ref "R34") (pin "1") (pinfunction "1_1") (pintype "passive"))
      (node (ref "R35") (pin "1") (pinfunction "1_1") (pintype "passive"))
      (node (ref "R36") (pin "1") (pinfunction "1_1") (pintype "passive"))
      (node (ref "R37") (pin "1") (pinfunction "1_1") (pintype "passive"))
      (node (ref "R5") (pin "2") (pinfunction "2_2") (pintype "passive"))
      (node (ref "R6") (pin "2") (pinfunction "2_2") (pintype "passive"))
    )
    (net (code "16") (name "Net-(C53-Pad1)") (class "Default")
      (node (ref "C53") (pin "1") (pinfunction "1_1") (pintype "passive"))
      (node (ref "C54") (pin "1") (pinfunction "1_1") (pintype "passive"))
      (node (ref "R11") (pin "1") (pinfunction "1_1") (pintype "passive"))
      (node (ref "R14") (pin "2") (pinfunction "2_2") (pintype "passive"))
    )
    (net (code "17") (name "Net-(C55-Pad1)") (class "Default")
      (node (ref "C55") (pin "1") (pinfunction "1_1") (pintype "passive"))
      (node (ref "C56") (pin "1") (pinfunction "1_1") (pintype "passive"))
      (node (ref "R14") (pin "1") (pinfunction "1_1") (pintype "passive"))
      (node (ref "R15") (pin "2") (pinfunction "2_2") (pintype "passive"))
      (node (ref "R21") (pin "2") (pinfunction "2_2") (pintype "passive"))
      (node (ref "R22") (pin "2") (pinfunction "2_2") (pintype "passive"))
      (node (ref "R25") (pin "3") (pinfunction "3_3") (pintype "passive"))
    )
    (net (code "18") (name "Net-(D2-PadA)") (class "Default")
      (node (ref "D2") (pin "A") (pinfunction "A_A") (pintype "passive"))
      (node (ref "D4") (pin "A") (pinfunction "A_A") (pintype "passive"))
    )
    (net (code "19") (name "Net-(D3-PadC)") (class "Default")
      (node (ref "D3") (pin "C") (pinfunction "C_C") (pintype "passive"))
      (node (ref "D5") (pin "C") (pinfunction "C_C") (pintype "passive"))
    )
    (net (code "20") (name "Net-(D6-PadA)") (class "Default")
      (node (ref "D6") (pin "A") (pinfunction "A_A") (pintype "passive"))
      (node (ref "D8") (pin "A") (pinfunction "A_A") (pintype "passive"))
    )
    (net (code "21") (name "Net-(D7-PadC)") (class "Default")
      (node (ref "D7") (pin "C") (pinfunction "C_C") (pintype "passive"))
      (node (ref "D9") (pin "C") (pinfunction "C_C") (pintype "passive"))
    )
    (net (code "22") (name "Net-(D10-PadA)") (class "Default")
      (node (ref "D10") (pin "A") (pinfunction "A_A") (pintype "passive"))
      (node (ref "D11") (pin "C") (pinfunction "C_C") (pintype "passive"))
      (node (ref "R1") (pin "2") (pinfunction "2_2") (pintype "passive"))
      (node (ref "R19") (pin "1") (pinfunction "1_1") (pintype "passive"))
      (node (ref "R2") (pin "2") (pinfunction "2_2") (pintype "passive"))
      (node (ref "R20") (pin "1") (pinfunction "1_1") (pintype "passive"))
      (node (ref "R3") (pin "2") (pinfunction "2_2") (pintype "passive"))
    )
    (net (code "23") (name "Net-(D10-PadC)") (class "Default")
      (node (ref "D10") (pin "C") (pinfunction "C_C") (pintype "passive"))
      (node (ref "D13") (pin "C") (pinfunction "C_C") (pintype "passive"))
    )
    (net (code "24") (name "Net-(D11-PadA)") (class "Default")
      (node (ref "D11") (pin "A") (pinfunction "A_A") (pintype "passive"))
      (node (ref "D12") (pin "A") (pinfunction "A_A") (pintype "passive"))
    )
    (net (code "25") (name "Net-(IC2-IN)") (class "Default")
      (node (ref "C47") (pin "2") (pinfunction "2_2") (pintype "passive"))
      (node (ref "IC2") (pin "1") (pinfunction "IN_1") (pintype "input"))
      (node (ref "IC2") (pin "3") (pinfunction "ONOFF_3") (pintype "power_in"))
      (node (ref "K2") (pin "24") (pinfunction "S_24") (pintype "passive"))
    )
    (net (code "26") (name "Net-(IC2-OUT)") (class "Default")
      (node (ref "C48") (pin "1") (pinfunction "1_1") (pintype "passive"))
      (node (ref "C57") (pin "1") (pinfunction "1_1") (pintype "passive"))
      (node (ref "IC2") (pin "5") (pinfunction "OUT_5") (pintype "output"))
      (node (ref "R13") (pin "2") (pinfunction "2_2") (pintype "passive"))
      (node (ref "R24") (pin "2") (pinfunction "2_2") (pintype "passive"))
    )
    (net (code "27") (name "Net-(JP4-Pad1)") (class "Default")
      (node (ref "JP4") (pin "1") (pinfunction "1_1") (pintype "bidirectional"))
      (node (ref "K3") (pin "O0") (pinfunction "O_O0") (pintype "passive"))
      (node (ref "K3") (pin "O1") (pinfunction "O_O1") (pintype "passive"))
    )
    (net (code "28") (name "Net-(JP9-Pad1)") (class "Default")
      (node (ref "JP9") (pin "1") (pinfunction "1_1") (pintype "bidirectional"))
      (node (ref "R18") (pin "1") (pinfunction "1_1") (pintype "passive"))
    )
    (net (code "29") (name "Net-(JP11-Pad1)") (class "Default")
      (node (ref "JP11") (pin "1") (pinfunction "1_1") (pintype "bidirectional"))
      (node (ref "K3") (pin "P0") (pinfunction "P_P0") (pintype "passive"))
      (node (ref "K3") (pin "P1") (pinfunction "P_P1") (pintype "passive"))
    )
    (net (code "30") (name "Net-(JP21-Pad1)") (class "Default")
      (node (ref "JP21") (pin "1") (pinfunction "1_1") (pintype "bidirectional"))
      (node (ref "R1") (pin "1") (pinfunction "1_1") (pintype "passive"))
      (node (ref "R2") (pin "1") (pinfunction "1_1") (pintype "passive"))
    )
    (net (code "31") (name "Net-(K2A-O)") (class "Default")
      (node (ref "JP7") (pin "1") (pinfunction "1_1") (pintype "bidirectional"))
      (node (ref "K2") (pin "12") (pinfunction "O_12") (pintype "passive"))
    )
    (net (code "32") (name "Net-(K2A-P)") (class "Default")
      (node (ref "JP1") (pin "1") (pinfunction "1_1") (pintype "bidirectional"))
      (node (ref "K2") (pin "11") (pinfunction "P_11") (pintype "passive"))
    )
    (net (code "33") (name "Net-(K2A-S)") (class "Default")
      (node (ref "JP19") (pin "1") (pinfunction "1_1") (pintype "bidirectional"))
      (node (ref "K2") (pin "14") (pinfunction "S_14") (pintype "passive"))
    )
    (net (code "34") (name "Net-(K2B-P)") (class "Default")
      (node (ref "C10") (pin "1") (pinfunction "1_1") (pintype "passive"))
      (node (ref "C9") (pin "1") (pinfunction "1_1") (pintype "passive"))
      (node (ref "D14") (pin "C") (pinfunction "C_C") (pintype "passive"))
      (node (ref "JP5") (pin "1") (pinfunction "1_1") (pintype "bidirectional"))
      (node (ref "K2") (pin "21") (pinfunction "P_21") (pintype "passive"))
      (node (ref "R17") (pin "1") (pinfunction "1_1") (pintype "passive"))
      (node (ref "T7") (pin "2") (pinfunction "S_2") (pintype "passive"))
    )
    (net (code "35") (name "Net-(K2C-1)") (class "Default")
      (node (ref "D16") (pin "C") (pinfunction "C_C") (pintype "passive"))
      (node (ref "JP17") (pin "1") (pinfunction "1_1") (pintype "bidirectional"))
      (node (ref "K2") (pin "A1") (pinfunction "1_A1") (pintype "passive"))
      (node (ref "T7") (pin "3") (pinfunction "D_3") (pintype "passive"))
    )
    (net (code "36") (name "Net-(K3B-S-PadS0)") (class "Default")
      (node (ref "K3") (pin "S0") (pinfunction "S_S0") (pintype "passive"))
      (node (ref "K3") (pin "S1") (pinfunction "S_S1") (pintype "passive"))
      (node (ref "TR4") (pin "P1") (pinfunction "P1_P1") (pintype "passive"))
    )
    (net (code "37") (name "Net-(L1-1)") (class "Default")
      (node (ref "C40") (pin "+") (pinfunction "+_+") (pintype "passive"))
      (node (ref "JP13") (pin "1") (pinfunction "1_1") (pintype "bidirectional"))
      (node (ref "JP16") (pin "1") (pinfunction "1_1") (pintype "bidirectional"))
      (node (ref "L1") (pin "P$1") (pinfunction "1_P$1") (pintype "passive"))
    )
    (net (code "38") (name "Net-(L1-2)") (class "Default")
      (node (ref "C11") (pin "1") (pinfunction "1_1") (pintype "passive"))
      (node (ref "C12") (pin "1") (pinfunction "1_1") (pintype "passive"))
      (node (ref "C13") (pin "1") (pinfunction "1_1") (pintype "passive"))
      (node (ref "C14") (pin "1") (pinfunction "1_1") (pintype "passive"))
      (node (ref "C15") (pin "2") (pinfunction "2_2") (pintype "passive"))
      (node (ref "C16") (pin "2") (pinfunction "2_2") (pintype "passive"))
      (node (ref "C17") (pin "2") (pinfunction "2_2") (pintype "passive"))
      (node (ref "C18") (pin "2") (pinfunction "2_2") (pintype "passive"))
      (node (ref "C19") (pin "2") (pinfunction "2_2") (pintype "passive"))
      (node (ref "C20") (pin "+") (pinfunction "+_+") (pintype "passive"))
      (node (ref "C21") (pin "+") (pinfunction "+_+") (pintype "passive"))
      (node (ref "C41") (pin "+") (pinfunction "+_+") (pintype "passive"))
      (node (ref "C8") (pin "1") (pinfunction "1_1") (pintype "passive"))
      (node (ref "L1") (pin "P$2") (pinfunction "2_P$2") (pintype "passive"))
      (node (ref "T1P3") (pin "P$1") (pinfunction "1_P$1") (pintype "bidirectional"))
      (node (ref "T1S4") (pin "P$1") (pinfunction "1_P$1") (pintype "bidirectional"))
    )
    (net (code "39") (name "Net-(R12-Pad2)") (class "Default")
      (node (ref "R12") (pin "2") (pinfunction "2_2") (pintype "passive"))
      (node (ref "R16") (pin "2") (pinfunction "2_2") (pintype "passive"))
    )
    (net (code "40") (name "Net-(R13-Pad1)") (class "Default")
      (node (ref "R13") (pin "1") (pinfunction "1_1") (pintype "passive"))
      (node (ref "R16") (pin "1") (pinfunction "1_1") (pintype "passive"))
    )
    (net (code "41") (name "Net-(R23-Pad2)") (class "Default")
      (node (ref "R23") (pin "2") (pinfunction "2_2") (pintype "passive"))
      (node (ref "R25") (pin "2") (pinfunction "2_2") (pintype "passive"))
    )
    (net (code "42") (name "Net-(R24-Pad1)") (class "Default")
      (node (ref "R24") (pin "1") (pinfunction "1_1") (pintype "passive"))
      (node (ref "R25") (pin "1") (pinfunction "1_1") (pintype "passive"))
    )
    (net (code "43") (name "Net-(T1-G1)") (class "Default")
      (node (ref "R32") (pin "2") (pinfunction "2_2") (pintype "passive"))
      (node (ref "R33") (pin "2") (pinfunction "2_2") (pintype "passive"))
      (node (ref "R34") (pin "2") (pinfunction "2_2") (pintype "passive"))
      (node (ref "T1") (pin "3") (pinfunction "G1_3") (pintype "passive"))
    )
    (net (code "44") (name "Net-(T1-G2)") (class "Default")
      (node (ref "R35") (pin "2") (pinfunction "2_2") (pintype "passive"))
      (node (ref "R36") (pin "2") (pinfunction "2_2") (pintype "passive"))
      (node (ref "R37") (pin "2") (pinfunction "2_2") (pintype "passive"))
      (node (ref "T1") (pin "4") (pinfunction "G2_4") (pintype "passive"))
    )
    (net (code "45") (name "Net-(T2-G1)") (class "Default")
      (node (ref "R26") (pin "2") (pinfunction "2_2") (pintype "passive"))
      (node (ref "R27") (pin "2") (pinfunction "2_2") (pintype "passive"))
      (node (ref "R28") (pin "2") (pinfunction "2_2") (pintype "passive"))
      (node (ref "T2") (pin "3") (pinfunction "G1_3") (pintype "passive"))
    )
    (net (code "46") (name "Net-(T2-G2)") (class "Default")
      (node (ref "R29") (pin "2") (pinfunction "2_2") (pintype "passive"))
      (node (ref "R30") (pin "2") (pinfunction "2_2") (pintype "passive"))
      (node (ref "R31") (pin "2") (pinfunction "2_2") (pintype "passive"))
      (node (ref "T2") (pin "4") (pinfunction "G2_4") (pintype "passive"))
    )
    (net (code "47") (name "Net-(T7-G)") (class "Default")
      (node (ref "C10") (pin "2") (pinfunction "2_2") (pintype "passive"))
      (node (ref "D14") (pin "A") (pinfunction "A_A") (pintype "passive"))
      (node (ref "R17") (pin "2") (pinfunction "2_2") (pintype "passive"))
      (node (ref "R18") (pin "2") (pinfunction "2_2") (pintype "passive"))
      (node (ref "T7") (pin "1") (pinfunction "G_1") (pintype "passive"))
    )
    (net (code "48") (name "Net-(TR1-P2)") (class "Default")
      (node (ref "R19") (pin "2") (pinfunction "2_2") (pintype "passive"))
      (node (ref "R20") (pin "2") (pinfunction "2_2") (pintype "passive"))
      (node (ref "TR1") (pin "IN") (pinfunction "P2_IN") (pintype "passive"))
    )
    (net (code "49") (name "Net-(TR1-S1)") (class "Default")
      (node (ref "C51") (pin "1") (pinfunction "1_1") (pintype "passive"))
      (node (ref "C52") (pin "1") (pinfunction "1_1") (pintype "passive"))
      (node (ref "C7") (pin "2") (pinfunction "2_2") (pintype "passive"))
      (node (ref "TR1") (pin "OUT1") (pinfunction "S1_OUT1") (pintype "passive"))
    )
    (net (code "50") (name "Net-(TR1-S2)") (class "Default")
      (node (ref "C49") (pin "1") (pinfunction "1_1") (pintype "passive"))
      (node (ref "C50") (pin "1") (pinfunction "1_1") (pintype "passive"))
      (node (ref "C7") (pin "1") (pinfunction "1_1") (pintype "passive"))
      (node (ref "TR1") (pin "OUT2") (pinfunction "S2_OUT2") (pintype "passive"))
    )
    (net (code "51") (name "unconnected-(FID1-PadP$1)") (class "Default")
      (node (ref "FID1") (pin "P$1") (pinfunction "P$1_P$1") (pintype "bidirectional"))
    )
    (net (code "52") (name "unconnected-(FID2-PadP$1)") (class "Default")
      (node (ref "FID2") (pin "P$1") (pinfunction "P$1_P$1") (pintype "bidirectional"))
    )
    (net (code "53") (name "unconnected-(K2B-O-Pad22)") (class "Default")
      (node (ref "K2") (pin "22") (pinfunction "O_22") (pintype "passive"))
    )
    (net (code "54") (name "unconnected-(T1-S-PadPAD)") (class "Default")
      (node (ref "T1") (pin "PAD") (pinfunction "S_PAD") (pintype "power_in"))
    )
    (net (code "55") (name "unconnected-(T2-S-PadPAD)") (class "Default")
      (node (ref "T2") (pin "PAD") (pinfunction "S_PAD") (pintype "power_in"))
    )
  )
)
